# nm_mcu.net
KiCad netlist of a schematic drawn in Altium Designer
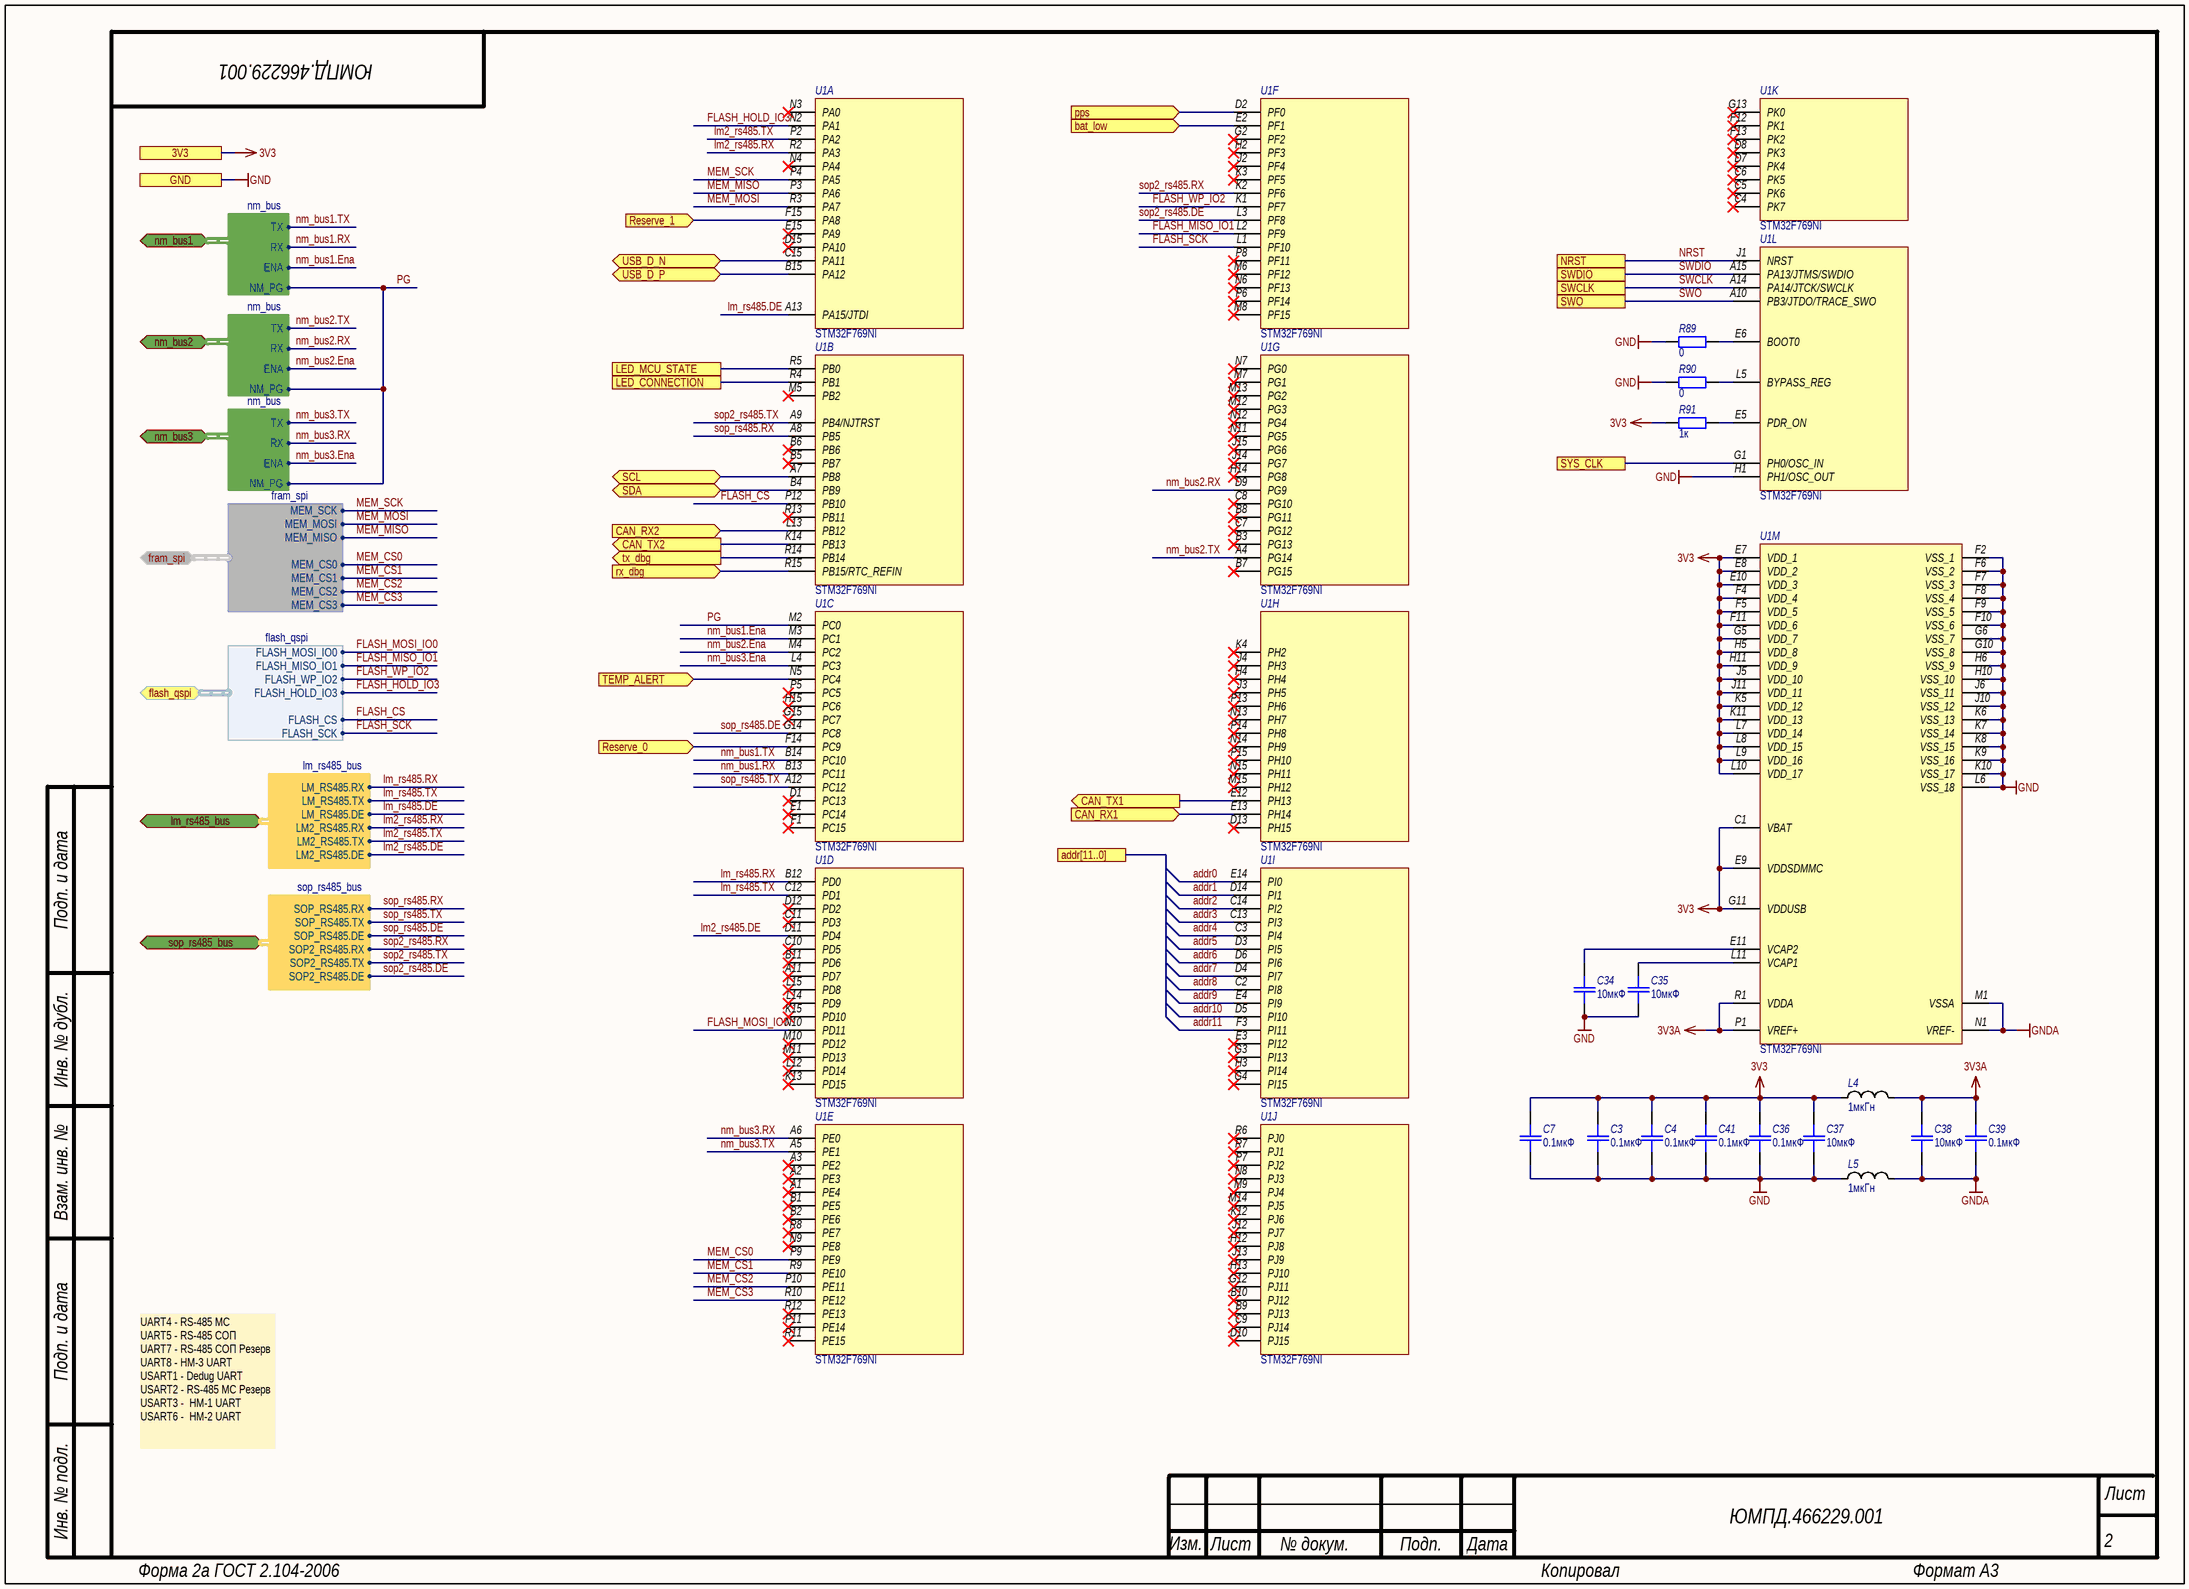
[diagram p0: nm_mcu.SchDoc]

(export (version "E")
  (design (tool "Eeschema 10.0.6"))
  (components
    (comp (ref "C3")
      (value "0.1мкФ")
      (footprint "SMD_C0603")
      (description "Capacitor")
      (libsource (lib "Passive") (part "Capacitor"))
    )
    (comp (ref "C4")
      (value "0.1мкФ")
      (footprint "SMD_C0603")
      (description "Capacitor")
      (libsource (lib "Passive") (part "Capacitor"))
    )
    (comp (ref "C7")
      (value "0.1мкФ")
      (footprint "SMD_C0603")
      (description "Capacitor")
      (libsource (lib "Passive") (part "Capacitor"))
    )
    (comp (ref "C34")
      (value "10мкФ")
      (footprint "SMD_C0603")
      (description "Capacitor")
      (libsource (lib "Passive") (part "Capacitor"))
    )
    (comp (ref "C35")
      (value "10мкФ")
      (footprint "SMD_C0603")
      (description "Capacitor")
      (libsource (lib "Passive") (part "Capacitor"))
    )
    (comp (ref "C36")
      (value "0.1мкФ")
      (footprint "SMD_C0603")
      (description "Capacitor")
      (libsource (lib "Passive") (part "Capacitor"))
    )
    (comp (ref "C37")
      (value "10мкФ")
      (footprint "SMD_C0603")
      (description "Capacitor")
      (libsource (lib "Passive") (part "Capacitor"))
    )
    (comp (ref "C38")
      (value "10мкФ")
      (footprint "SMD_C0603")
      (description "Capacitor")
      (libsource (lib "Passive") (part "Capacitor"))
    )
    (comp (ref "C39")
      (value "0.1мкФ")
      (footprint "SMD_C0603")
      (description "Capacitor")
      (libsource (lib "Passive") (part "Capacitor"))
    )
    (comp (ref "C41")
      (value "0.1мкФ")
      (footprint "SMD_C0603")
      (description "Capacitor")
      (libsource (lib "Passive") (part "Capacitor"))
    )
    (comp (ref "L4")
      (value "1мкГн")
      (footprint "SMD_0805")
      (description "Inductor")
      (libsource (lib "Passive") (part "Inductor"))
    )
    (comp (ref "L5")
      (value "1мкГн")
      (footprint "SMD_0805")
      (description "Inductor")
      (libsource (lib "Passive") (part "Inductor"))
    )
    (comp (ref "R89")
      (value "0")
      (footprint "SMD_0603")
      (description "Resistor")
      (libsource (lib "Passive") (part "Resistor"))
    )
    (comp (ref "R90")
      (value "0")
      (footprint "SMD_0603")
      (description "Resistor")
      (libsource (lib "Passive") (part "Resistor"))
    )
    (comp (ref "R91")
      (value "1к")
      (footprint "SMD_0603")
      (description "Resistor")
      (libsource (lib "Passive") (part "Resistor"))
    )
    (comp (ref "U1")
      (value "STM32F769NI")
      (footprint "BGA216C80P15X15_1300X1300X110")
      (fields (field (name "НАИМЕНОВАНИЕ") "STM32F769NI"))
      (libsource (lib "STM32F769NI") (part "STM32F769NI"))
    )
  )
  (nets
    (net (code "6") (name "/CAN_RX1") (class "Default")
      (node (ref "U1") (pin "E13") (pinfunction "PH14_E13") (pintype "passive"))
    )
    (net (code "7") (name "/CAN_RX2") (class "Default")
      (node (ref "U1") (pin "L13") (pinfunction "PB12_L13") (pintype "passive"))
    )
    (net (code "8") (name "/CAN_TX1") (class "Default")
      (node (ref "U1") (pin "E12") (pinfunction "PH13_E12") (pintype "passive"))
    )
    (net (code "9") (name "/CAN_TX2") (class "Default")
      (node (ref "U1") (pin "K14") (pinfunction "PB13_K14") (pintype "passive"))
    )
    (net (code "10") (name "/FLASH_CS") (class "Default")
      (node (ref "U1") (pin "P12") (pinfunction "PB10_P12") (pintype "passive"))
    )
    (net (code "11") (name "/FLASH_HOLD_IO3") (class "Default")
      (node (ref "U1") (pin "N2") (pinfunction "PA1_N2") (pintype "passive"))
    )
    (net (code "12") (name "/FLASH_MISO_IO1") (class "Default")
      (node (ref "U1") (pin "L2") (pinfunction "PF9_L2") (pintype "passive"))
    )
    (net (code "13") (name "/FLASH_MOSI_IO0") (class "Default")
      (node (ref "U1") (pin "N10") (pinfunction "PD11_N10") (pintype "passive"))
    )
    (net (code "14") (name "/FLASH_SCK") (class "Default")
      (node (ref "U1") (pin "L1") (pinfunction "PF10_L1") (pintype "passive"))
    )
    (net (code "15") (name "/FLASH_WP_IO2") (class "Default")
      (node (ref "U1") (pin "K1") (pinfunction "PF7_K1") (pintype "passive"))
    )
    (net (code "16") (name "/LED_CONNECTION") (class "Default")
      (node (ref "U1") (pin "R4") (pinfunction "PB1_R4") (pintype "passive"))
    )
    (net (code "17") (name "/LED_MCU_STATE") (class "Default")
      (node (ref "U1") (pin "R5") (pinfunction "PB0_R5") (pintype "passive"))
    )
    (net (code "18") (name "/MEM_CS0") (class "Default")
      (node (ref "U1") (pin "P9") (pinfunction "PE9_P9") (pintype "passive"))
    )
    (net (code "19") (name "/MEM_CS1") (class "Default")
      (node (ref "U1") (pin "R9") (pinfunction "PE10_R9") (pintype "passive"))
    )
    (net (code "20") (name "/MEM_CS2") (class "Default")
      (node (ref "U1") (pin "P10") (pinfunction "PE11_P10") (pintype "passive"))
    )
    (net (code "21") (name "/MEM_CS3") (class "Default")
      (node (ref "U1") (pin "R10") (pinfunction "PE12_R10") (pintype "passive"))
    )
    (net (code "22") (name "/MEM_MISO") (class "Default")
      (node (ref "U1") (pin "P3") (pinfunction "PA6_P3") (pintype "passive"))
    )
    (net (code "23") (name "/MEM_MOSI") (class "Default")
      (node (ref "U1") (pin "R3") (pinfunction "PA7_R3") (pintype "passive"))
    )
    (net (code "24") (name "/MEM_SCK") (class "Default")
      (node (ref "U1") (pin "P4") (pinfunction "PA5_P4") (pintype "passive"))
    )
    (net (code "25") (name "/NRST") (class "Default")
      (node (ref "U1") (pin "J1") (pinfunction "NRST_J1") (pintype "passive"))
    )
    (net (code "26") (name "/PG") (class "Default")
      (node (ref "U1") (pin "M2") (pinfunction "PC0_M2") (pintype "passive"))
    )
    (net (code "27") (name "/Reserve_0") (class "Default")
      (node (ref "U1") (pin "F14") (pinfunction "PC9_F14") (pintype "passive"))
    )
    (net (code "28") (name "/Reserve_1") (class "Default")
      (node (ref "U1") (pin "F15") (pinfunction "PA8_F15") (pintype "passive"))
    )
    (net (code "29") (name "/SCL") (class "Default")
      (node (ref "U1") (pin "A7") (pinfunction "PB8_A7") (pintype "passive"))
    )
    (net (code "30") (name "/SDA") (class "Default")
      (node (ref "U1") (pin "B4") (pinfunction "PB9_B4") (pintype "passive"))
    )
    (net (code "31") (name "/SWCLK") (class "Default")
      (node (ref "U1") (pin "A14") (pinfunction "PA14/JTCK/SWCLK_A14") (pintype "passive"))
    )
    (net (code "32") (name "/SWDIO") (class "Default")
      (node (ref "U1") (pin "A15") (pinfunction "PA13/JTMS/SWDIO_A15") (pintype "passive"))
    )
    (net (code "33") (name "/SWO") (class "Default")
      (node (ref "U1") (pin "A10") (pinfunction "PB3/JTDO/TRACE_SWO_A10") (pintype "passive"))
    )
    (net (code "34") (name "/SYS_CLK") (class "Default")
      (node (ref "U1") (pin "G1") (pinfunction "PH0/OSC_IN_G1") (pintype "passive"))
    )
    (net (code "35") (name "/TEMP_ALERT") (class "Default")
      (node (ref "U1") (pin "N5") (pinfunction "PC4_N5") (pintype "passive"))
    )
    (net (code "36") (name "/USB_D_N") (class "Default")
      (node (ref "U1") (pin "C15") (pinfunction "PA11_C15") (pintype "passive"))
    )
    (net (code "37") (name "/USB_D_P") (class "Default")
      (node (ref "U1") (pin "B15") (pinfunction "PA12_B15") (pintype "passive"))
    )
    (net (code "38") (name "/addr0") (class "Default")
      (node (ref "U1") (pin "E14") (pinfunction "PI0_E14") (pintype "passive"))
    )
    (net (code "39") (name "/addr1") (class "Default")
      (node (ref "U1") (pin "D14") (pinfunction "PI1_D14") (pintype "passive"))
    )
    (net (code "40") (name "/addr2") (class "Default")
      (node (ref "U1") (pin "C14") (pinfunction "PI2_C14") (pintype "passive"))
    )
    (net (code "41") (name "/addr3") (class "Default")
      (node (ref "U1") (pin "C13") (pinfunction "PI3_C13") (pintype "passive"))
    )
    (net (code "42") (name "/addr4") (class "Default")
      (node (ref "U1") (pin "C3") (pinfunction "PI4_C3") (pintype "passive"))
    )
    (net (code "43") (name "/addr5") (class "Default")
      (node (ref "U1") (pin "D3") (pinfunction "PI5_D3") (pintype "passive"))
    )
    (net (code "44") (name "/addr6") (class "Default")
      (node (ref "U1") (pin "D6") (pinfunction "PI6_D6") (pintype "passive"))
    )
    (net (code "45") (name "/addr7") (class "Default")
      (node (ref "U1") (pin "D4") (pinfunction "PI7_D4") (pintype "passive"))
    )
    (net (code "46") (name "/addr8") (class "Default")
      (node (ref "U1") (pin "C2") (pinfunction "PI8_C2") (pintype "passive"))
    )
    (net (code "47") (name "/addr9") (class "Default")
      (node (ref "U1") (pin "E4") (pinfunction "PI9_E4") (pintype "passive"))
    )
    (net (code "48") (name "/addr10") (class "Default")
      (node (ref "U1") (pin "D5") (pinfunction "PI10_D5") (pintype "passive"))
    )
    (net (code "49") (name "/addr11") (class "Default")
      (node (ref "U1") (pin "F3") (pinfunction "PI11_F3") (pintype "passive"))
    )
    (net (code "51") (name "/bat_low") (class "Default")
      (node (ref "U1") (pin "E2") (pinfunction "PF1_E2") (pintype "passive"))
    )
    (net (code "52") (name "/lm2_rs485.DE") (class "Default")
      (node (ref "U1") (pin "D11") (pinfunction "PD4_D11") (pintype "passive"))
    )
    (net (code "53") (name "/lm2_rs485.RX") (class "Default")
      (node (ref "U1") (pin "R2") (pinfunction "PA3_R2") (pintype "passive"))
    )
    (net (code "54") (name "/lm2_rs485.TX") (class "Default")
      (node (ref "U1") (pin "P2") (pinfunction "PA2_P2") (pintype "passive"))
    )
    (net (code "55") (name "/lm_rs485.DE") (class "Default")
      (node (ref "U1") (pin "A13") (pinfunction "PA15/JTDI_A13") (pintype "passive"))
    )
    (net (code "56") (name "/lm_rs485.RX") (class "Default")
      (node (ref "U1") (pin "B12") (pinfunction "PD0_B12") (pintype "passive"))
    )
    (net (code "57") (name "/lm_rs485.TX") (class "Default")
      (node (ref "U1") (pin "C12") (pinfunction "PD1_C12") (pintype "passive"))
    )
    (net (code "58") (name "/nm_bus1.Ena") (class "Default")
      (node (ref "U1") (pin "M3") (pinfunction "PC1_M3") (pintype "passive"))
    )
    (net (code "59") (name "/nm_bus1.RX") (class "Default")
      (node (ref "U1") (pin "B13") (pinfunction "PC11_B13") (pintype "passive"))
    )
    (net (code "60") (name "/nm_bus1.TX") (class "Default")
      (node (ref "U1") (pin "B14") (pinfunction "PC10_B14") (pintype "passive"))
    )
    (net (code "61") (name "/nm_bus2.Ena") (class "Default")
      (node (ref "U1") (pin "M4") (pinfunction "PC2_M4") (pintype "passive"))
    )
    (net (code "62") (name "/nm_bus2.RX") (class "Default")
      (node (ref "U1") (pin "D9") (pinfunction "PG9_D9") (pintype "passive"))
    )
    (net (code "63") (name "/nm_bus2.TX") (class "Default")
      (node (ref "U1") (pin "A4") (pinfunction "PG14_A4") (pintype "passive"))
    )
    (net (code "64") (name "/nm_bus3.Ena") (class "Default")
      (node (ref "U1") (pin "L4") (pinfunction "PC3_L4") (pintype "passive"))
    )
    (net (code "65") (name "/nm_bus3.RX") (class "Default")
      (node (ref "U1") (pin "A6") (pinfunction "PE0_A6") (pintype "passive"))
    )
    (net (code "66") (name "/nm_bus3.TX") (class "Default")
      (node (ref "U1") (pin "A5") (pinfunction "PE1_A5") (pintype "passive"))
    )
    (net (code "67") (name "/pps") (class "Default")
      (node (ref "U1") (pin "D2") (pinfunction "PF0_D2") (pintype "passive"))
    )
    (net (code "68") (name "/rx_dbg") (class "Default")
      (node (ref "U1") (pin "R15") (pinfunction "PB15/RTC_REFIN_R15") (pintype "passive"))
    )
    (net (code "69") (name "/sop2_rs485.DE") (class "Default")
      (node (ref "U1") (pin "L3") (pinfunction "PF8_L3") (pintype "passive"))
    )
    (net (code "70") (name "/sop2_rs485.RX") (class "Default")
      (node (ref "U1") (pin "K2") (pinfunction "PF6_K2") (pintype "passive"))
    )
    (net (code "71") (name "/sop2_rs485.TX") (class "Default")
      (node (ref "U1") (pin "A9") (pinfunction "PB4/NJTRST_A9") (pintype "passive"))
    )
    (net (code "72") (name "/sop_rs485.DE") (class "Default")
      (node (ref "U1") (pin "G14") (pinfunction "PC8_G14") (pintype "passive"))
    )
    (net (code "73") (name "/sop_rs485.RX") (class "Default")
      (node (ref "U1") (pin "A8") (pinfunction "PB5_A8") (pintype "passive"))
    )
    (net (code "74") (name "/sop_rs485.TX") (class "Default")
      (node (ref "U1") (pin "A12") (pinfunction "PC12_A12") (pintype "passive"))
    )
    (net (code "75") (name "/tx_dbg") (class "Default")
      (node (ref "U1") (pin "R14") (pinfunction "PB14_R14") (pintype "passive"))
    )
    (net (code "81") (name "3V3") (class "Default")
      (node (ref "C3") (pin "2") (pinfunction "2_2") (pintype "passive"))
      (node (ref "C36") (pin "2") (pinfunction "2_2") (pintype "passive"))
      (node (ref "C37") (pin "2") (pinfunction "2_2") (pintype "passive"))
      (node (ref "C4") (pin "2") (pinfunction "2_2") (pintype "passive"))
      (node (ref "C41") (pin "2") (pinfunction "2_2") (pintype "passive"))
      (node (ref "C7") (pin "2") (pinfunction "2_2") (pintype "passive"))
      (node (ref "L4") (pin "1") (pinfunction "1_1") (pintype "passive"))
      (node (ref "R91") (pin "1") (pinfunction "1_1") (pintype "passive"))
      (node (ref "U1") (pin "C1") (pinfunction "VBAT_C1") (pintype "passive"))
      (node (ref "U1") (pin "E10") (pinfunction "VDD_3_E10") (pintype "passive"))
      (node (ref "U1") (pin "E7") (pinfunction "VDD_1_E7") (pintype "passive"))
      (node (ref "U1") (pin "E8") (pinfunction "VDD_2_E8") (pintype "passive"))
      (node (ref "U1") (pin "E9") (pinfunction "VDDSDMMC_E9") (pintype "passive"))
      (node (ref "U1") (pin "F11") (pinfunction "VDD_6_F11") (pintype "passive"))
      (node (ref "U1") (pin "F4") (pinfunction "VDD_4_F4") (pintype "passive"))
      (node (ref "U1") (pin "F5") (pinfunction "VDD_5_F5") (pintype "passive"))
      (node (ref "U1") (pin "G11") (pinfunction "VDDUSB_G11") (pintype "passive"))
      (node (ref "U1") (pin "G5") (pinfunction "VDD_7_G5") (pintype "passive"))
      (node (ref "U1") (pin "H11") (pinfunction "VDD_9_H11") (pintype "passive"))
      (node (ref "U1") (pin "H5") (pinfunction "VDD_8_H5") (pintype "passive"))
      (node (ref "U1") (pin "J11") (pinfunction "VDD_11_J11") (pintype "passive"))
      (node (ref "U1") (pin "J5") (pinfunction "VDD_10_J5") (pintype "passive"))
      (node (ref "U1") (pin "K11") (pinfunction "VDD_13_K11") (pintype "passive"))
      (node (ref "U1") (pin "K5") (pinfunction "VDD_12_K5") (pintype "passive"))
      (node (ref "U1") (pin "L10") (pinfunction "VDD_17_L10") (pintype "passive"))
      (node (ref "U1") (pin "L7") (pinfunction "VDD_14_L7") (pintype "passive"))
      (node (ref "U1") (pin "L8") (pinfunction "VDD_15_L8") (pintype "passive"))
      (node (ref "U1") (pin "L9") (pinfunction "VDD_16_L9") (pintype "passive"))
    )
    (net (code "82") (name "3V3A") (class "Default")
      (node (ref "C38") (pin "2") (pinfunction "2_2") (pintype "passive"))
      (node (ref "C39") (pin "2") (pinfunction "2_2") (pintype "passive"))
      (node (ref "L4") (pin "2") (pinfunction "2_2") (pintype "passive"))
      (node (ref "U1") (pin "P1") (pinfunction "VREF+_P1") (pintype "passive"))
      (node (ref "U1") (pin "R1") (pinfunction "VDDA_R1") (pintype "passive"))
    )
    (net (code "83") (name "GND") (class "Default")
      (node (ref "C3") (pin "1") (pinfunction "1_1") (pintype "passive"))
      (node (ref "C34") (pin "1") (pinfunction "1_1") (pintype "passive"))
      (node (ref "C35") (pin "1") (pinfunction "1_1") (pintype "passive"))
      (node (ref "C36") (pin "1") (pinfunction "1_1") (pintype "passive"))
      (node (ref "C37") (pin "1") (pinfunction "1_1") (pintype "passive"))
      (node (ref "C4") (pin "1") (pinfunction "1_1") (pintype "passive"))
      (node (ref "C41") (pin "1") (pinfunction "1_1") (pintype "passive"))
      (node (ref "C7") (pin "1") (pinfunction "1_1") (pintype "passive"))
      (node (ref "L5") (pin "1") (pinfunction "1_1") (pintype "passive"))
      (node (ref "R89") (pin "1") (pinfunction "1_1") (pintype "passive"))
      (node (ref "R90") (pin "1") (pinfunction "1_1") (pintype "passive"))
      (node (ref "U1") (pin "F10") (pinfunction "VSS_6_F10") (pintype "passive"))
      (node (ref "U1") (pin "F2") (pinfunction "VSS_1_F2") (pintype "passive"))
      (node (ref "U1") (pin "F6") (pinfunction "VSS_2_F6") (pintype "passive"))
      (node (ref "U1") (pin "F7") (pinfunction "VSS_3_F7") (pintype "passive"))
      (node (ref "U1") (pin "F8") (pinfunction "VSS_4_F8") (pintype "passive"))
      (node (ref "U1") (pin "F9") (pinfunction "VSS_5_F9") (pintype "passive"))
      (node (ref "U1") (pin "G10") (pinfunction "VSS_8_G10") (pintype "passive"))
      (node (ref "U1") (pin "G6") (pinfunction "VSS_7_G6") (pintype "passive"))
      (node (ref "U1") (pin "H1") (pinfunction "PH1/OSC_OUT_H1") (pintype "passive"))
      (node (ref "U1") (pin "H10") (pinfunction "VSS_10_H10") (pintype "passive"))
      (node (ref "U1") (pin "H6") (pinfunction "VSS_9_H6") (pintype "passive"))
      (node (ref "U1") (pin "J10") (pinfunction "VSS_12_J10") (pintype "passive"))
      (node (ref "U1") (pin "J6") (pinfunction "VSS_11_J6") (pintype "passive"))
      (node (ref "U1") (pin "K10") (pinfunction "VSS_17_K10") (pintype "passive"))
      (node (ref "U1") (pin "K6") (pinfunction "VSS_13_K6") (pintype "passive"))
      (node (ref "U1") (pin "K7") (pinfunction "VSS_14_K7") (pintype "passive"))
      (node (ref "U1") (pin "K8") (pinfunction "VSS_15_K8") (pintype "passive"))
      (node (ref "U1") (pin "K9") (pinfunction "VSS_16_K9") (pintype "passive"))
      (node (ref "U1") (pin "L6") (pinfunction "VSS_18_L6") (pintype "passive"))
    )
    (net (code "84") (name "GNDA") (class "Default")
      (node (ref "C38") (pin "1") (pinfunction "1_1") (pintype "passive"))
      (node (ref "C39") (pin "1") (pinfunction "1_1") (pintype "passive"))
      (node (ref "L5") (pin "2") (pinfunction "2_2") (pintype "passive"))
      (node (ref "U1") (pin "M1") (pinfunction "VSSA_M1") (pintype "passive"))
      (node (ref "U1") (pin "N1") (pinfunction "VREF-_N1") (pintype "passive"))
    )
    (net (code "85") (name "Net-(U1L-BOOT0)") (class "Default")
      (node (ref "R89") (pin "2") (pinfunction "2_2") (pintype "passive"))
      (node (ref "U1") (pin "E6") (pinfunction "BOOT0_E6") (pintype "passive"))
    )
    (net (code "86") (name "Net-(U1L-BYPASS_REG)") (class "Default")
      (node (ref "R90") (pin "2") (pinfunction "2_2") (pintype "passive"))
      (node (ref "U1") (pin "L5") (pinfunction "BYPASS_REG_L5") (pintype "passive"))
    )
    (net (code "87") (name "Net-(U1L-PDR_ON)") (class "Default")
      (node (ref "R91") (pin "2") (pinfunction "2_2") (pintype "passive"))
      (node (ref "U1") (pin "E5") (pinfunction "PDR_ON_E5") (pintype "passive"))
    )
    (net (code "88") (name "Net-(U1M-VCAP1)") (class "Default")
      (node (ref "C35") (pin "2") (pinfunction "2_2") (pintype "passive"))
      (node (ref "U1") (pin "L11") (pinfunction "VCAP1_L11") (pintype "passive"))
    )
    (net (code "89") (name "Net-(U1M-VCAP2)") (class "Default")
      (node (ref "C34") (pin "2") (pinfunction "2_2") (pintype "passive"))
      (node (ref "U1") (pin "E11") (pinfunction "VCAP2_E11") (pintype "passive"))
    )
    (net (code "90") (name "unconnected-(U1A-PA0-PadN3)") (class "Default")
      (node (ref "U1") (pin "N3") (pinfunction "PA0_N3") (pintype "passive+no_connect"))
    )
    (net (code "91") (name "unconnected-(U1A-PA4-PadN4)") (class "Default")
      (node (ref "U1") (pin "N4") (pinfunction "PA4_N4") (pintype "passive+no_connect"))
    )
    (net (code "92") (name "unconnected-(U1A-PA9-PadE15)") (class "Default")
      (node (ref "U1") (pin "E15") (pinfunction "PA9_E15") (pintype "passive+no_connect"))
    )
    (net (code "93") (name "unconnected-(U1A-PA10-PadD15)") (class "Default")
      (node (ref "U1") (pin "D15") (pinfunction "PA10_D15") (pintype "passive+no_connect"))
    )
    (net (code "94") (name "unconnected-(U1B-PB2-PadM5)") (class "Default")
      (node (ref "U1") (pin "M5") (pinfunction "PB2_M5") (pintype "passive+no_connect"))
    )
    (net (code "95") (name "unconnected-(U1B-PB6-PadB6)") (class "Default")
      (node (ref "U1") (pin "B6") (pinfunction "PB6_B6") (pintype "passive+no_connect"))
    )
    (net (code "96") (name "unconnected-(U1B-PB7-PadB5)") (class "Default")
      (node (ref "U1") (pin "B5") (pinfunction "PB7_B5") (pintype "passive+no_connect"))
    )
    (net (code "97") (name "unconnected-(U1B-PB11-PadR13)") (class "Default")
      (node (ref "U1") (pin "R13") (pinfunction "PB11_R13") (pintype "passive+no_connect"))
    )
    (net (code "98") (name "unconnected-(U1C-PC5-PadP5)") (class "Default")
      (node (ref "U1") (pin "P5") (pinfunction "PC5_P5") (pintype "passive+no_connect"))
    )
    (net (code "99") (name "unconnected-(U1C-PC6-PadH15)") (class "Default")
      (node (ref "U1") (pin "H15") (pinfunction "PC6_H15") (pintype "passive+no_connect"))
    )
    (net (code "100") (name "unconnected-(U1C-PC7-PadG15)") (class "Default")
      (node (ref "U1") (pin "G15") (pinfunction "PC7_G15") (pintype "passive+no_connect"))
    )
    (net (code "101") (name "unconnected-(U1C-PC13-PadD1)") (class "Default")
      (node (ref "U1") (pin "D1") (pinfunction "PC13_D1") (pintype "passive+no_connect"))
    )
    (net (code "102") (name "unconnected-(U1C-PC14-PadE1)") (class "Default")
      (node (ref "U1") (pin "E1") (pinfunction "PC14_E1") (pintype "passive+no_connect"))
    )
    (net (code "103") (name "unconnected-(U1C-PC15-PadF1)") (class "Default")
      (node (ref "U1") (pin "F1") (pinfunction "PC15_F1") (pintype "passive+no_connect"))
    )
    (net (code "104") (name "unconnected-(U1D-PD2-PadD12)") (class "Default")
      (node (ref "U1") (pin "D12") (pinfunction "PD2_D12") (pintype "passive+no_connect"))
    )
    (net (code "105") (name "unconnected-(U1D-PD3-PadC11)") (class "Default")
      (node (ref "U1") (pin "C11") (pinfunction "PD3_C11") (pintype "passive+no_connect"))
    )
    (net (code "106") (name "unconnected-(U1D-PD5-PadC10)") (class "Default")
      (node (ref "U1") (pin "C10") (pinfunction "PD5_C10") (pintype "passive+no_connect"))
    )
    (net (code "107") (name "unconnected-(U1D-PD6-PadB11)") (class "Default")
      (node (ref "U1") (pin "B11") (pinfunction "PD6_B11") (pintype "passive+no_connect"))
    )
    (net (code "108") (name "unconnected-(U1D-PD7-PadA11)") (class "Default")
      (node (ref "U1") (pin "A11") (pinfunction "PD7_A11") (pintype "passive+no_connect"))
    )
    (net (code "109") (name "unconnected-(U1D-PD8-PadL15)") (class "Default")
      (node (ref "U1") (pin "L15") (pinfunction "PD8_L15") (pintype "passive+no_connect"))
    )
    (net (code "110") (name "unconnected-(U1D-PD9-PadL14)") (class "Default")
      (node (ref "U1") (pin "L14") (pinfunction "PD9_L14") (pintype "passive+no_connect"))
    )
    (net (code "111") (name "unconnected-(U1D-PD10-PadK15)") (class "Default")
      (node (ref "U1") (pin "K15") (pinfunction "PD10_K15") (pintype "passive+no_connect"))
    )
    (net (code "112") (name "unconnected-(U1D-PD12-PadM10)") (class "Default")
      (node (ref "U1") (pin "M10") (pinfunction "PD12_M10") (pintype "passive+no_connect"))
    )
    (net (code "113") (name "unconnected-(U1D-PD13-PadM11)") (class "Default")
      (node (ref "U1") (pin "M11") (pinfunction "PD13_M11") (pintype "passive+no_connect"))
    )
    (net (code "114") (name "unconnected-(U1D-PD14-PadL12)") (class "Default")
      (node (ref "U1") (pin "L12") (pinfunction "PD14_L12") (pintype "passive+no_connect"))
    )
    (net (code "115") (name "unconnected-(U1D-PD15-PadK13)") (class "Default")
      (node (ref "U1") (pin "K13") (pinfunction "PD15_K13") (pintype "passive+no_connect"))
    )
    (net (code "116") (name "unconnected-(U1E-PE2-PadA3)") (class "Default")
      (node (ref "U1") (pin "A3") (pinfunction "PE2_A3") (pintype "passive+no_connect"))
    )
    (net (code "117") (name "unconnected-(U1E-PE3-PadA2)") (class "Default")
      (node (ref "U1") (pin "A2") (pinfunction "PE3_A2") (pintype "passive+no_connect"))
    )
    (net (code "118") (name "unconnected-(U1E-PE4-PadA1)") (class "Default")
      (node (ref "U1") (pin "A1") (pinfunction "PE4_A1") (pintype "passive+no_connect"))
    )
    (net (code "119") (name "unconnected-(U1E-PE5-PadB1)") (class "Default")
      (node (ref "U1") (pin "B1") (pinfunction "PE5_B1") (pintype "passive+no_connect"))
    )
    (net (code "120") (name "unconnected-(U1E-PE6-PadB2)") (class "Default")
      (node (ref "U1") (pin "B2") (pinfunction "PE6_B2") (pintype "passive+no_connect"))
    )
    (net (code "121") (name "unconnected-(U1E-PE7-PadR8)") (class "Default")
      (node (ref "U1") (pin "R8") (pinfunction "PE7_R8") (pintype "passive+no_connect"))
    )
    (net (code "122") (name "unconnected-(U1E-PE8-PadN9)") (class "Default")
      (node (ref "U1") (pin "N9") (pinfunction "PE8_N9") (pintype "passive+no_connect"))
    )
    (net (code "123") (name "unconnected-(U1E-PE13-PadR12)") (class "Default")
      (node (ref "U1") (pin "R12") (pinfunction "PE13_R12") (pintype "passive+no_connect"))
    )
    (net (code "124") (name "unconnected-(U1E-PE14-PadP11)") (class "Default")
      (node (ref "U1") (pin "P11") (pinfunction "PE14_P11") (pintype "passive+no_connect"))
    )
    (net (code "125") (name "unconnected-(U1E-PE15-PadR11)") (class "Default")
      (node (ref "U1") (pin "R11") (pinfunction "PE15_R11") (pintype "passive+no_connect"))
    )
    (net (code "126") (name "unconnected-(U1F-PF2-PadG2)") (class "Default")
      (node (ref "U1") (pin "G2") (pinfunction "PF2_G2") (pintype "passive+no_connect"))
    )
    (net (code "127") (name "unconnected-(U1F-PF3-PadH2)") (class "Default")
      (node (ref "U1") (pin "H2") (pinfunction "PF3_H2") (pintype "passive+no_connect"))
    )
    (net (code "128") (name "unconnected-(U1F-PF4-PadJ2)") (class "Default")
      (node (ref "U1") (pin "J2") (pinfunction "PF4_J2") (pintype "passive+no_connect"))
    )
    (net (code "129") (name "unconnected-(U1F-PF5-PadK3)") (class "Default")
      (node (ref "U1") (pin "K3") (pinfunction "PF5_K3") (pintype "passive+no_connect"))
    )
    (net (code "130") (name "unconnected-(U1F-PF11-PadP8)") (class "Default")
      (node (ref "U1") (pin "P8") (pinfunction "PF11_P8") (pintype "passive+no_connect"))
    )
    (net (code "131") (name "unconnected-(U1F-PF12-PadM6)") (class "Default")
      (node (ref "U1") (pin "M6") (pinfunction "PF12_M6") (pintype "passive+no_connect"))
    )
    (net (code "132") (name "unconnected-(U1F-PF13-PadN6)") (class "Default")
      (node (ref "U1") (pin "N6") (pinfunction "PF13_N6") (pintype "passive+no_connect"))
    )
    (net (code "133") (name "unconnected-(U1F-PF14-PadP6)") (class "Default")
      (node (ref "U1") (pin "P6") (pinfunction "PF14_P6") (pintype "passive+no_connect"))
    )
    (net (code "134") (name "unconnected-(U1F-PF15-PadM8)") (class "Default")
      (node (ref "U1") (pin "M8") (pinfunction "PF15_M8") (pintype "passive+no_connect"))
    )
    (net (code "135") (name "unconnected-(U1G-PG0-PadN7)") (class "Default")
      (node (ref "U1") (pin "N7") (pinfunction "PG0_N7") (pintype "passive+no_connect"))
    )
    (net (code "136") (name "unconnected-(U1G-PG1-PadM7)") (class "Default")
      (node (ref "U1") (pin "M7") (pinfunction "PG1_M7") (pintype "passive+no_connect"))
    )
    (net (code "137") (name "unconnected-(U1G-PG2-PadM13)") (class "Default")
      (node (ref "U1") (pin "M13") (pinfunction "PG2_M13") (pintype "passive+no_connect"))
    )
    (net (code "138") (name "unconnected-(U1G-PG3-PadM12)") (class "Default")
      (node (ref "U1") (pin "M12") (pinfunction "PG3_M12") (pintype "passive+no_connect"))
    )
    (net (code "139") (name "unconnected-(U1G-PG4-PadN12)") (class "Default")
      (node (ref "U1") (pin "N12") (pinfunction "PG4_N12") (pintype "passive+no_connect"))
    )
    (net (code "140") (name "unconnected-(U1G-PG5-PadN11)") (class "Default")
      (node (ref "U1") (pin "N11") (pinfunction "PG5_N11") (pintype "passive+no_connect"))
    )
    (net (code "141") (name "unconnected-(U1G-PG6-PadJ15)") (class "Default")
      (node (ref "U1") (pin "J15") (pinfunction "PG6_J15") (pintype "passive+no_connect"))
    )
    (net (code "142") (name "unconnected-(U1G-PG7-PadJ14)") (class "Default")
      (node (ref "U1") (pin "J14") (pinfunction "PG7_J14") (pintype "passive+no_connect"))
    )
    (net (code "143") (name "unconnected-(U1G-PG8-PadH14)") (class "Default")
      (node (ref "U1") (pin "H14") (pinfunction "PG8_H14") (pintype "passive+no_connect"))
    )
    (net (code "144") (name "unconnected-(U1G-PG10-PadC8)") (class "Default")
      (node (ref "U1") (pin "C8") (pinfunction "PG10_C8") (pintype "passive+no_connect"))
    )
    (net (code "145") (name "unconnected-(U1G-PG11-PadB8)") (class "Default")
      (node (ref "U1") (pin "B8") (pinfunction "PG11_B8") (pintype "passive+no_connect"))
    )
    (net (code "146") (name "unconnected-(U1G-PG12-PadC7)") (class "Default")
      (node (ref "U1") (pin "C7") (pinfunction "PG12_C7") (pintype "passive+no_connect"))
    )
    (net (code "147") (name "unconnected-(U1G-PG13-PadB3)") (class "Default")
      (node (ref "U1") (pin "B3") (pinfunction "PG13_B3") (pintype "passive+no_connect"))
    )
    (net (code "148") (name "unconnected-(U1G-PG15-PadB7)") (class "Default")
      (node (ref "U1") (pin "B7") (pinfunction "PG15_B7") (pintype "passive+no_connect"))
    )
    (net (code "149") (name "unconnected-(U1H-PH2-PadK4)") (class "Default")
      (node (ref "U1") (pin "K4") (pinfunction "PH2_K4") (pintype "passive+no_connect"))
    )
    (net (code "150") (name "unconnected-(U1H-PH3-PadJ4)") (class "Default")
      (node (ref "U1") (pin "J4") (pinfunction "PH3_J4") (pintype "passive+no_connect"))
    )
    (net (code "151") (name "unconnected-(U1H-PH4-PadH4)") (class "Default")
      (node (ref "U1") (pin "H4") (pinfunction "PH4_H4") (pintype "passive+no_connect"))
    )
    (net (code "152") (name "unconnected-(U1H-PH5-PadJ3)") (class "Default")
      (node (ref "U1") (pin "J3") (pinfunction "PH5_J3") (pintype "passive+no_connect"))
    )
    (net (code "153") (name "unconnected-(U1H-PH6-PadP13)") (class "Default")
      (node (ref "U1") (pin "P13") (pinfunction "PH6_P13") (pintype "passive+no_connect"))
    )
    (net (code "154") (name "unconnected-(U1H-PH7-PadN13)") (class "Default")
      (node (ref "U1") (pin "N13") (pinfunction "PH7_N13") (pintype "passive+no_connect"))
    )
    (net (code "155") (name "unconnected-(U1H-PH8-PadP14)") (class "Default")
      (node (ref "U1") (pin "P14") (pinfunction "PH8_P14") (pintype "passive+no_connect"))
    )
    (net (code "156") (name "unconnected-(U1H-PH9-PadN14)") (class "Default")
      (node (ref "U1") (pin "N14") (pinfunction "PH9_N14") (pintype "passive+no_connect"))
    )
    (net (code "157") (name "unconnected-(U1H-PH10-PadP15)") (class "Default")
      (node (ref "U1") (pin "P15") (pinfunction "PH10_P15") (pintype "passive+no_connect"))
    )
    (net (code "158") (name "unconnected-(U1H-PH11-PadN15)") (class "Default")
      (node (ref "U1") (pin "N15") (pinfunction "PH11_N15") (pintype "passive+no_connect"))
    )
    (net (code "159") (name "unconnected-(U1H-PH12-PadM15)") (class "Default")
      (node (ref "U1") (pin "M15") (pinfunction "PH12_M15") (pintype "passive+no_connect"))
    )
    (net (code "160") (name "unconnected-(U1H-PH15-PadD13)") (class "Default")
      (node (ref "U1") (pin "D13") (pinfunction "PH15_D13") (pintype "passive+no_connect"))
    )
    (net (code "161") (name "unconnected-(U1I-PI12-PadE3)") (class "Default")
      (node (ref "U1") (pin "E3") (pinfunction "PI12_E3") (pintype "passive+no_connect"))
    )
    (net (code "162") (name "unconnected-(U1I-PI13-PadG3)") (class "Default")
      (node (ref "U1") (pin "G3") (pinfunction "PI13_G3") (pintype "passive+no_connect"))
    )
    (net (code "163") (name "unconnected-(U1I-PI14-PadH3)") (class "Default")
      (node (ref "U1") (pin "H3") (pinfunction "PI14_H3") (pintype "passive+no_connect"))
    )
    (net (code "164") (name "unconnected-(U1I-PI15-PadG4)") (class "Default")
      (node (ref "U1") (pin "G4") (pinfunction "PI15_G4") (pintype "passive+no_connect"))
    )
    (net (code "165") (name "unconnected-(U1J-PJ0-PadR6)") (class "Default")
      (node (ref "U1") (pin "R6") (pinfunction "PJ0_R6") (pintype "passive+no_connect"))
    )
    (net (code "166") (name "unconnected-(U1J-PJ1-PadR7)") (class "Default")
      (node (ref "U1") (pin "R7") (pinfunction "PJ1_R7") (pintype "passive+no_connect"))
    )
    (net (code "167") (name "unconnected-(U1J-PJ2-PadP7)") (class "Default")
      (node (ref "U1") (pin "P7") (pinfunction "PJ2_P7") (pintype "passive+no_connect"))
    )
    (net (code "168") (name "unconnected-(U1J-PJ3-PadN8)") (class "Default")
      (node (ref "U1") (pin "N8") (pinfunction "PJ3_N8") (pintype "passive+no_connect"))
    )
    (net (code "169") (name "unconnected-(U1J-PJ4-PadM9)") (class "Default")
      (node (ref "U1") (pin "M9") (pinfunction "PJ4_M9") (pintype "passive+no_connect"))
    )
    (net (code "170") (name "unconnected-(U1J-PJ5-PadM14)") (class "Default")
      (node (ref "U1") (pin "M14") (pinfunction "PJ5_M14") (pintype "passive+no_connect"))
    )
    (net (code "171") (name "unconnected-(U1J-PJ6-PadK12)") (class "Default")
      (node (ref "U1") (pin "K12") (pinfunction "PJ6_K12") (pintype "passive+no_connect"))
    )
    (net (code "172") (name "unconnected-(U1J-PJ7-PadJ12)") (class "Default")
      (node (ref "U1") (pin "J12") (pinfunction "PJ7_J12") (pintype "passive+no_connect"))
    )
    (net (code "173") (name "unconnected-(U1J-PJ8-PadH12)") (class "Default")
      (node (ref "U1") (pin "H12") (pinfunction "PJ8_H12") (pintype "passive+no_connect"))
    )
    (net (code "174") (name "unconnected-(U1J-PJ9-PadJ13)") (class "Default")
      (node (ref "U1") (pin "J13") (pinfunction "PJ9_J13") (pintype "passive+no_connect"))
    )
    (net (code "175") (name "unconnected-(U1J-PJ10-PadH13)") (class "Default")
      (node (ref "U1") (pin "H13") (pinfunction "PJ10_H13") (pintype "passive+no_connect"))
    )
    (net (code "176") (name "unconnected-(U1J-PJ11-PadG12)") (class "Default")
      (node (ref "U1") (pin "G12") (pinfunction "PJ11_G12") (pintype "passive+no_connect"))
    )
    (net (code "177") (name "unconnected-(U1J-PJ12-PadB10)") (class "Default")
      (node (ref "U1") (pin "B10") (pinfunction "PJ12_B10") (pintype "passive+no_connect"))
    )
    (net (code "178") (name "unconnected-(U1J-PJ13-PadB9)") (class "Default")
      (node (ref "U1") (pin "B9") (pinfunction "PJ13_B9") (pintype "passive+no_connect"))
    )
    (net (code "179") (name "unconnected-(U1J-PJ14-PadC9)") (class "Default")
      (node (ref "U1") (pin "C9") (pinfunction "PJ14_C9") (pintype "passive+no_connect"))
    )
    (net (code "180") (name "unconnected-(U1J-PJ15-PadD10)") (class "Default")
      (node (ref "U1") (pin "D10") (pinfunction "PJ15_D10") (pintype "passive+no_connect"))
    )
    (net (code "181") (name "unconnected-(U1K-PK0-PadG13)") (class "Default")
      (node (ref "U1") (pin "G13") (pinfunction "PK0_G13") (pintype "passive+no_connect"))
    )
    (net (code "182") (name "unconnected-(U1K-PK1-PadF12)") (class "Default")
      (node (ref "U1") (pin "F12") (pinfunction "PK1_F12") (pintype "passive+no_connect"))
    )
    (net (code "183") (name "unconnected-(U1K-PK2-PadF13)") (class "Default")
      (node (ref "U1") (pin "F13") (pinfunction "PK2_F13") (pintype "passive+no_connect"))
    )
    (net (code "184") (name "unconnected-(U1K-PK3-PadD8)") (class "Default")
      (node (ref "U1") (pin "D8") (pinfunction "PK3_D8") (pintype "passive+no_connect"))
    )
    (net (code "185") (name "unconnected-(U1K-PK4-PadD7)") (class "Default")
      (node (ref "U1") (pin "D7") (pinfunction "PK4_D7") (pintype "passive+no_connect"))
    )
    (net (code "186") (name "unconnected-(U1K-PK5-PadC6)") (class "Default")
      (node (ref "U1") (pin "C6") (pinfunction "PK5_C6") (pintype "passive+no_connect"))
    )
    (net (code "187") (name "unconnected-(U1K-PK6-PadC5)") (class "Default")
      (node (ref "U1") (pin "C5") (pinfunction "PK6_C5") (pintype "passive+no_connect"))
    )
    (net (code "188") (name "unconnected-(U1K-PK7-PadC4)") (class "Default")
      (node (ref "U1") (pin "C4") (pinfunction "PK7_C4") (pintype "passive+no_connect"))
    )
  )
)
